# TSOP1838.net
KiCad netlist of a schematic drawn in Altium Designer
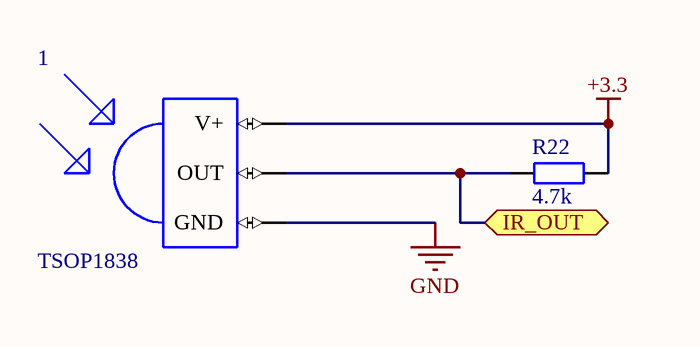
[diagram p0: TSOP1838.SchDoc]

(export (version "E")
  (design (tool "Eeschema 10.0.6"))
  (components
    (comp (ref "1")
      (value "TSOP1838")
      (footprint "TSOP18XX")
      (description "IR Remote Receiver 38KHz 35m 3-Pin")
      (fields (field (name "MF") "Vishay"))
      (libsource (lib "TSOP1838") (part "TSOP1838"))
    )
    (comp (ref "R22")
      (value "4.7k")
      (footprint "tro smd 0603")
      (description "Dán")
      (libsource (lib "Altium_Lib_by_KhueNguyenCreator") (part "Tro 0603 5% 4.7k"))
    )
  )
  (nets
    (net (code "1") (name "+3.3") (class "Default")
      (node (ref "1") (pin "VCC") (pinfunction "V+_VCC") (pintype "bidirectional"))
      (node (ref "R22") (pin "2") (pinfunction "2_2") (pintype "passive"))
    )
    (net (code "2") (name "/IR_OUT") (class "Default")
      (node (ref "1") (pin "OUT") (pinfunction "OUT_OUT") (pintype "bidirectional"))
      (node (ref "R22") (pin "1") (pinfunction "1_1") (pintype "passive"))
    )
    (net (code "3") (name "GND") (class "Default")
      (node (ref "1") (pin "GND") (pinfunction "GND_GND") (pintype "bidirectional"))
    )
  )
)
